# final_schematic.net
KiCad netlist of a schematic drawn in EAGLE
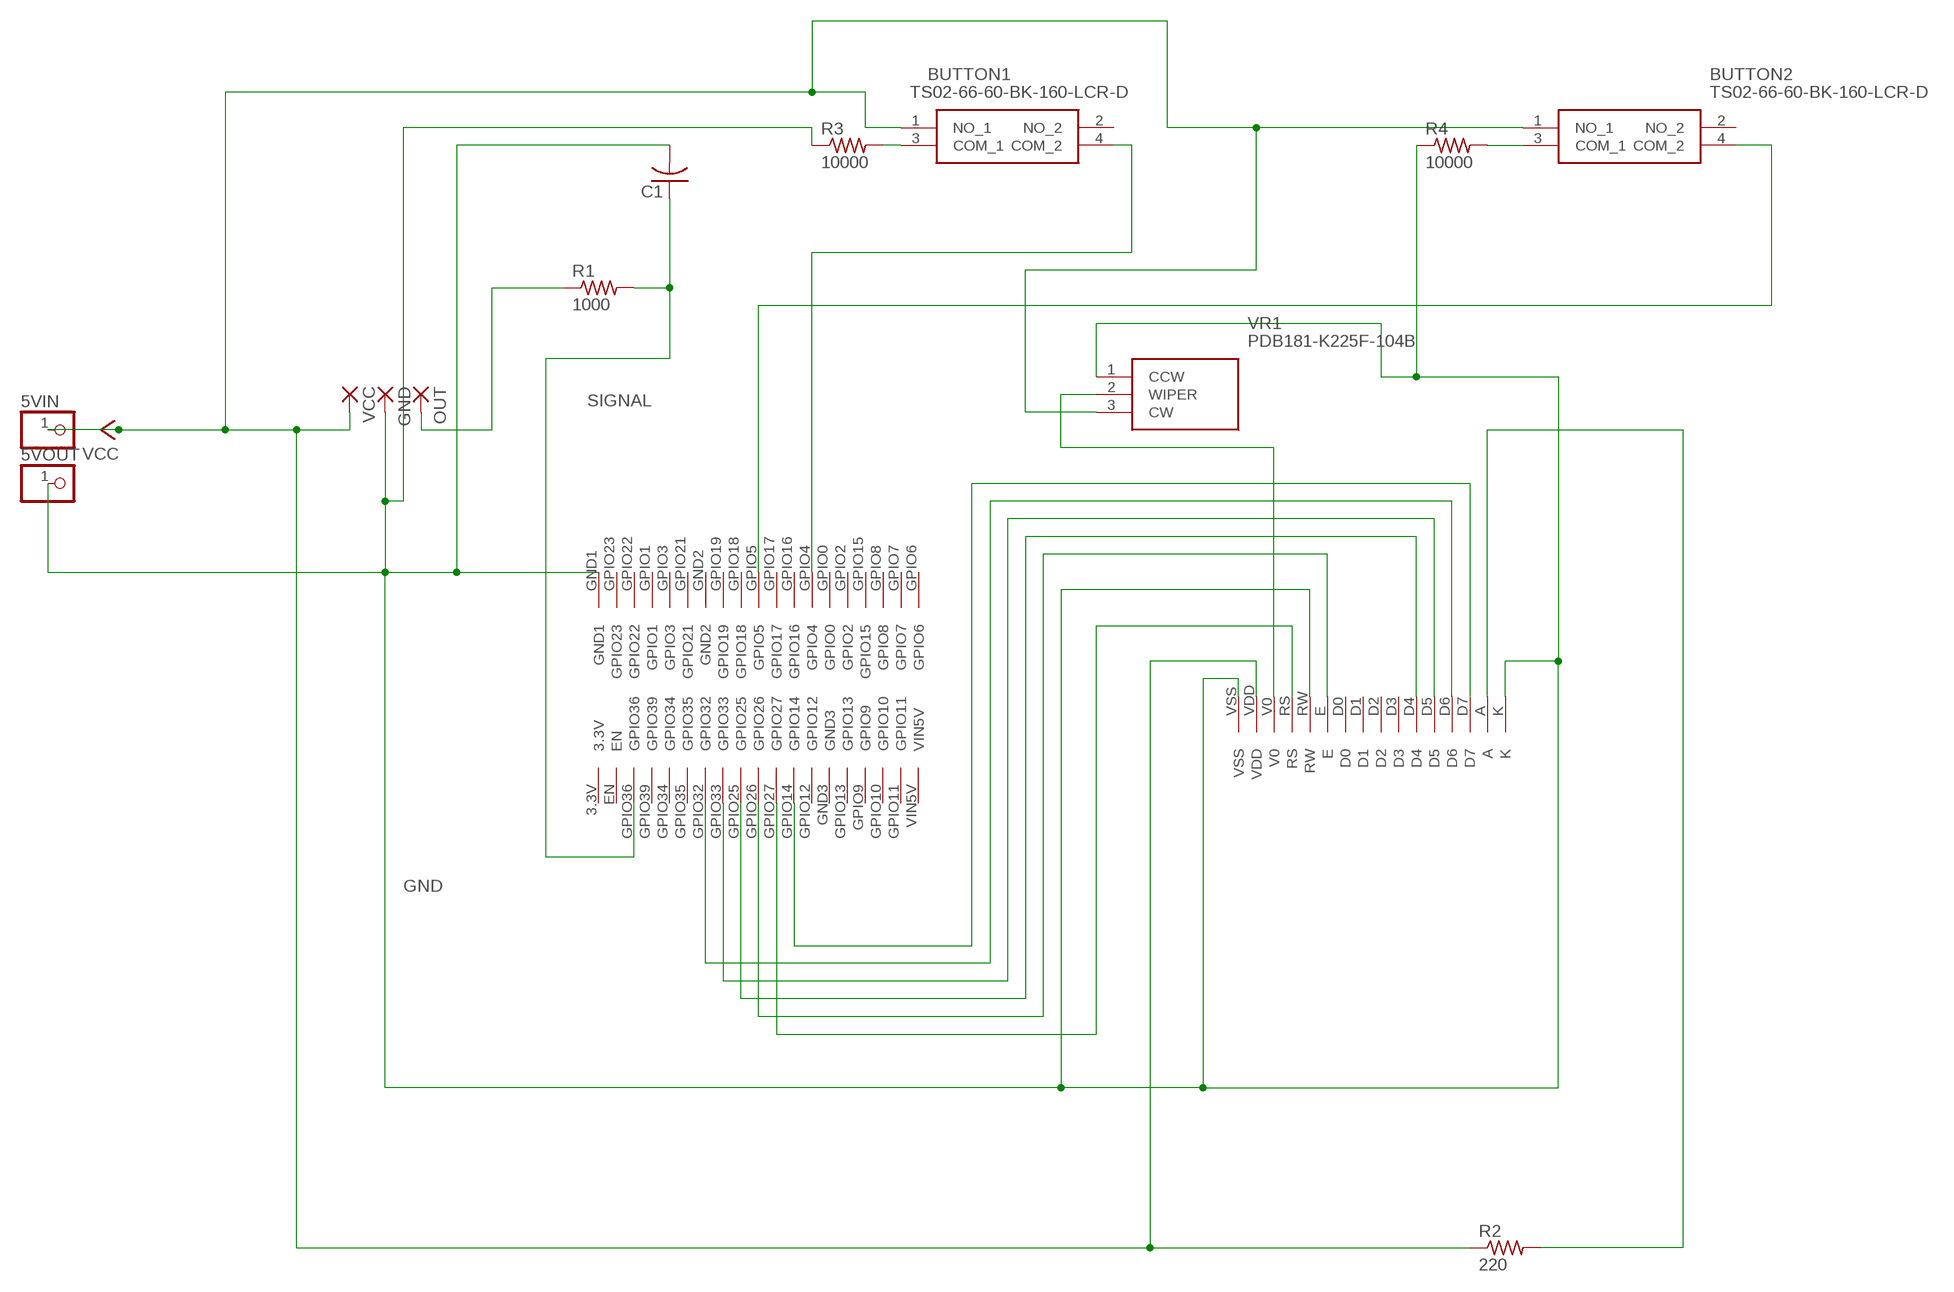
[diagram p0: schematic, sheet 1]

(export (version "E")
  (design (tool "Eeschema 10.0.6"))
  (components
    (comp (ref "5VIN")
      (value "PINHD-1X1")
      (footprint "eagle-import:1X01")
      (libsource (lib "eagle-import") (part "PINHD-1X1"))
    )
    (comp (ref "5VOUT")
      (value "PINHD-1X1")
      (footprint "eagle-import:1X01")
      (libsource (lib "eagle-import") (part "PINHD-1X1"))
    )
    (comp (ref "BUTTON1")
      (value "TS02-66-60-BK-160-LCR-D")
      (footprint "eagle-import:TS026660BK160LCRD")
      (fields (field (name "MOUSER_PART_NUMBER") "179-TS026660BK160LCR"))
      (libsource (lib "eagle-import") (part "TS02-66-60-BK-160-LCR-D"))
    )
    (comp (ref "BUTTON2")
      (value "TS02-66-60-BK-160-LCR-D")
      (footprint "eagle-import:TS026660BK160LCRD")
      (fields (field (name "MOUSER_PART_NUMBER") "179-TS026660BK160LCR"))
      (libsource (lib "eagle-import") (part "TS02-66-60-BK-160-LCR-D"))
    )
    (comp (ref "C1")
      (value "C-USC0805")
      (footprint "eagle-import:C0805")
      (libsource (lib "eagle-import") (part "C-USC0805"))
    )
    (comp (ref "GND")
      (value "1,6/0,8")
      (footprint "eagle-import:1,6_0,8")
      (libsource (lib "eagle-import") (part "1,6/0,8"))
    )
    (comp (ref "OUT")
      (value "1,6/0,8")
      (footprint "eagle-import:1,6_0,8")
      (libsource (lib "eagle-import") (part "1,6/0,8"))
    )
    (comp (ref "R1")
      (value "1000")
      (footprint "eagle-import:R0805")
      (libsource (lib "eagle-import") (part "R-US_R0805"))
    )
    (comp (ref "R2")
      (value "220")
      (footprint "eagle-import:R0805")
      (libsource (lib "eagle-import") (part "R-US_R0805"))
    )
    (comp (ref "R3")
      (value "10000")
      (footprint "eagle-import:R0805")
      (libsource (lib "eagle-import") (part "R-US_R0805"))
    )
    (comp (ref "R4")
      (value "10000")
      (footprint "eagle-import:R0805")
      (libsource (lib "eagle-import") (part "R-US_R0805"))
    )
    (comp (ref "U$1")
      (value "HILETGO")
      (footprint "eagle-import:HILETGO")
      (libsource (lib "eagle-import") (part "HILETGO"))
    )
    (comp (ref "U$2")
      (value "LCD")
      (footprint "eagle-import:LCD")
      (libsource (lib "eagle-import") (part "LCD"))
    )
    (comp (ref "VCC")
      (value "1,6/0,8")
      (footprint "eagle-import:1,6_0,8")
      (libsource (lib "eagle-import") (part "1,6/0,8"))
    )
    (comp (ref "VR1")
      (value "PDB181-K225F-104B")
      (footprint "eagle-import:PDB181K225F104B")
      (fields (field (name "MOUSER_PART_NUMBER") "652-PDB181-K225F104B"))
      (libsource (lib "eagle-import") (part "PDB181-K225F-104B"))
    )
  )
  (nets
    (net (code "1") (name "/GND") (class "Default")
      (node (ref "5VOUT") (pin "1") (pinfunction "1_1") (pintype "passive"))
      (node (ref "C1") (pin "2") (pinfunction "2_2") (pintype "passive"))
      (node (ref "GND") (pin "1") (pinfunction "P_1") (pintype "passive"))
      (node (ref "R3") (pin "1") (pinfunction "1_1") (pintype "passive"))
      (node (ref "R4") (pin "1") (pinfunction "1_1") (pintype "passive"))
      (node (ref "U$1") (pin "GND1") (pinfunction "GND1_GND1") (pintype "bidirectional"))
      (node (ref "U$2") (pin "K") (pinfunction "K_K") (pintype "bidirectional"))
      (node (ref "U$2") (pin "RW") (pinfunction "RW_RW") (pintype "bidirectional"))
      (node (ref "U$2") (pin "VSS") (pinfunction "VSS_VSS") (pintype "bidirectional"))
      (node (ref "VR1") (pin "1") (pinfunction "CCW_1") (pintype "bidirectional"))
    )
    (net (code "2") (name "/SIGNAL") (class "Default")
      (node (ref "C1") (pin "1") (pinfunction "1_1") (pintype "passive"))
      (node (ref "R1") (pin "2") (pinfunction "2_2") (pintype "passive"))
      (node (ref "U$1") (pin "GPIO36") (pinfunction "GPIO36_GPIO36") (pintype "bidirectional"))
    )
    (net (code "3") (name "Net-(BUTTON1-COM_1)") (class "Default")
      (node (ref "BUTTON1") (pin "3") (pinfunction "COM_1_3") (pintype "bidirectional"))
      (node (ref "R3") (pin "2") (pinfunction "2_2") (pintype "passive"))
    )
    (net (code "4") (name "Net-(BUTTON1-COM_2)") (class "Default")
      (node (ref "BUTTON1") (pin "4") (pinfunction "COM_2_4") (pintype "bidirectional"))
      (node (ref "U$1") (pin "GPIO4") (pinfunction "GPIO4_GPIO4") (pintype "bidirectional"))
    )
    (net (code "5") (name "Net-(BUTTON2-COM_1)") (class "Default")
      (node (ref "BUTTON2") (pin "3") (pinfunction "COM_1_3") (pintype "bidirectional"))
      (node (ref "R4") (pin "2") (pinfunction "2_2") (pintype "passive"))
    )
    (net (code "6") (name "Net-(BUTTON2-COM_2)") (class "Default")
      (node (ref "BUTTON2") (pin "4") (pinfunction "COM_2_4") (pintype "bidirectional"))
      (node (ref "U$1") (pin "GPIO5") (pinfunction "GPIO5_GPIO5") (pintype "bidirectional"))
    )
    (net (code "7") (name "Net-(OUT-P)") (class "Default")
      (node (ref "OUT") (pin "1") (pinfunction "P_1") (pintype "passive"))
      (node (ref "R1") (pin "1") (pinfunction "1_1") (pintype "passive"))
    )
    (net (code "8") (name "Net-(R2-Pad2)") (class "Default")
      (node (ref "R2") (pin "2") (pinfunction "2_2") (pintype "passive"))
      (node (ref "U$2") (pin "A") (pinfunction "A_A") (pintype "bidirectional"))
    )
    (net (code "9") (name "Net-(U$1-PadGPIO14)") (class "Default")
      (node (ref "U$1") (pin "GPIO14") (pinfunction "GPIO14_GPIO14") (pintype "bidirectional"))
      (node (ref "U$2") (pin "D7") (pinfunction "D7_D7") (pintype "bidirectional"))
    )
    (net (code "10") (name "Net-(U$1-PadGPIO25)") (class "Default")
      (node (ref "U$1") (pin "GPIO25") (pinfunction "GPIO25_GPIO25") (pintype "bidirectional"))
      (node (ref "U$2") (pin "D4") (pinfunction "D4_D4") (pintype "bidirectional"))
    )
    (net (code "11") (name "Net-(U$1-PadGPIO26)") (class "Default")
      (node (ref "U$1") (pin "GPIO26") (pinfunction "GPIO26_GPIO26") (pintype "bidirectional"))
      (node (ref "U$2") (pin "E") (pinfunction "E_E") (pintype "bidirectional"))
    )
    (net (code "12") (name "Net-(U$1-PadGPIO27)") (class "Default")
      (node (ref "U$1") (pin "GPIO27") (pinfunction "GPIO27_GPIO27") (pintype "bidirectional"))
      (node (ref "U$2") (pin "RS") (pinfunction "RS_RS") (pintype "bidirectional"))
    )
    (net (code "13") (name "Net-(U$1-PadGPIO32)") (class "Default")
      (node (ref "U$1") (pin "GPIO32") (pinfunction "GPIO32_GPIO32") (pintype "bidirectional"))
      (node (ref "U$2") (pin "D6") (pinfunction "D6_D6") (pintype "bidirectional"))
    )
    (net (code "14") (name "Net-(U$1-PadGPIO33)") (class "Default")
      (node (ref "U$1") (pin "GPIO33") (pinfunction "GPIO33_GPIO33") (pintype "bidirectional"))
      (node (ref "U$2") (pin "D5") (pinfunction "D5_D5") (pintype "bidirectional"))
    )
    (net (code "15") (name "Net-(VR1-WIPER)") (class "Default")
      (node (ref "U$2") (pin "V0") (pinfunction "V0_V0") (pintype "bidirectional"))
      (node (ref "VR1") (pin "2") (pinfunction "WIPER_2") (pintype "bidirectional"))
    )
    (net (code "16") (name "VCC") (class "Default")
      (node (ref "5VIN") (pin "1") (pinfunction "1_1") (pintype "passive"))
      (node (ref "BUTTON1") (pin "1") (pinfunction "NO_1_1") (pintype "bidirectional"))
      (node (ref "BUTTON2") (pin "1") (pinfunction "NO_1_1") (pintype "bidirectional"))
      (node (ref "R2") (pin "1") (pinfunction "1_1") (pintype "passive"))
      (node (ref "U$2") (pin "VDD") (pinfunction "VDD_VDD") (pintype "bidirectional"))
      (node (ref "VCC") (pin "1") (pinfunction "P_1") (pintype "passive"))
      (node (ref "VR1") (pin "3") (pinfunction "CW_3") (pintype "bidirectional"))
    )
    (net (code "17") (name "unconnected-(BUTTON1-NO_2-Pad2)") (class "Default")
      (node (ref "BUTTON1") (pin "2") (pinfunction "NO_2_2") (pintype "bidirectional"))
    )
    (net (code "18") (name "unconnected-(BUTTON2-NO_2-Pad2)") (class "Default")
      (node (ref "BUTTON2") (pin "2") (pinfunction "NO_2_2") (pintype "bidirectional"))
    )
    (net (code "19") (name "unconnected-(U$1-Pad3.3V)") (class "Default")
      (node (ref "U$1") (pin "3.3V") (pinfunction "3.3V_3.3V") (pintype "bidirectional"))
    )
    (net (code "20") (name "unconnected-(U$1-PadEN)") (class "Default")
      (node (ref "U$1") (pin "EN") (pinfunction "EN_EN") (pintype "bidirectional"))
    )
    (net (code "21") (name "unconnected-(U$1-PadGND2)") (class "Default")
      (node (ref "U$1") (pin "GND2") (pinfunction "GND2_GND2") (pintype "bidirectional"))
    )
    (net (code "22") (name "unconnected-(U$1-PadGND3)") (class "Default")
      (node (ref "U$1") (pin "GND3") (pinfunction "GND3_GND3") (pintype "bidirectional"))
    )
    (net (code "23") (name "unconnected-(U$1-PadGPIO0)") (class "Default")
      (node (ref "U$1") (pin "GPIO0") (pinfunction "GPIO0_GPIO0") (pintype "bidirectional"))
    )
    (net (code "24") (name "unconnected-(U$1-PadGPIO1)") (class "Default")
      (node (ref "U$1") (pin "GPIO1") (pinfunction "GPIO1_GPIO1") (pintype "bidirectional"))
    )
    (net (code "25") (name "unconnected-(U$1-PadGPIO2)") (class "Default")
      (node (ref "U$1") (pin "GPIO2") (pinfunction "GPIO2_GPIO2") (pintype "bidirectional"))
    )
    (net (code "26") (name "unconnected-(U$1-PadGPIO3)") (class "Default")
      (node (ref "U$1") (pin "GPIO3") (pinfunction "GPIO3_GPIO3") (pintype "bidirectional"))
    )
    (net (code "27") (name "unconnected-(U$1-PadGPIO6)") (class "Default")
      (node (ref "U$1") (pin "GPIO6") (pinfunction "GPIO6_GPIO6") (pintype "bidirectional"))
    )
    (net (code "28") (name "unconnected-(U$1-PadGPIO7)") (class "Default")
      (node (ref "U$1") (pin "GPIO7") (pinfunction "GPIO7_GPIO7") (pintype "bidirectional"))
    )
    (net (code "29") (name "unconnected-(U$1-PadGPIO8)") (class "Default")
      (node (ref "U$1") (pin "GPIO8") (pinfunction "GPIO8_GPIO8") (pintype "bidirectional"))
    )
    (net (code "30") (name "unconnected-(U$1-PadGPIO9)") (class "Default")
      (node (ref "U$1") (pin "GPIO9") (pinfunction "GPIO9_GPIO9") (pintype "bidirectional"))
    )
    (net (code "31") (name "unconnected-(U$1-PadGPIO10)") (class "Default")
      (node (ref "U$1") (pin "GPIO10") (pinfunction "GPIO10_GPIO10") (pintype "bidirectional"))
    )
    (net (code "32") (name "unconnected-(U$1-PadGPIO11)") (class "Default")
      (node (ref "U$1") (pin "GPIO11") (pinfunction "GPIO11_GPIO11") (pintype "bidirectional"))
    )
    (net (code "33") (name "unconnected-(U$1-PadGPIO12)") (class "Default")
      (node (ref "U$1") (pin "GPIO12") (pinfunction "GPIO12_GPIO12") (pintype "bidirectional"))
    )
    (net (code "34") (name "unconnected-(U$1-PadGPIO13)") (class "Default")
      (node (ref "U$1") (pin "GPIO13") (pinfunction "GPIO13_GPIO13") (pintype "bidirectional"))
    )
    (net (code "35") (name "unconnected-(U$1-PadGPIO15)") (class "Default")
      (node (ref "U$1") (pin "GPIO15") (pinfunction "GPIO15_GPIO15") (pintype "bidirectional"))
    )
    (net (code "36") (name "unconnected-(U$1-PadGPIO16)") (class "Default")
      (node (ref "U$1") (pin "GPIO16") (pinfunction "GPIO16_GPIO16") (pintype "bidirectional"))
    )
    (net (code "37") (name "unconnected-(U$1-PadGPIO17)") (class "Default")
      (node (ref "U$1") (pin "GPIO17") (pinfunction "GPIO17_GPIO17") (pintype "bidirectional"))
    )
    (net (code "38") (name "unconnected-(U$1-PadGPIO18)") (class "Default")
      (node (ref "U$1") (pin "GPIO18") (pinfunction "GPIO18_GPIO18") (pintype "bidirectional"))
    )
    (net (code "39") (name "unconnected-(U$1-PadGPIO19)") (class "Default")
      (node (ref "U$1") (pin "GPIO19") (pinfunction "GPIO19_GPIO19") (pintype "bidirectional"))
    )
    (net (code "40") (name "unconnected-(U$1-PadGPIO21)") (class "Default")
      (node (ref "U$1") (pin "GPIO21") (pinfunction "GPIO21_GPIO21") (pintype "bidirectional"))
    )
    (net (code "41") (name "unconnected-(U$1-PadGPIO22)") (class "Default")
      (node (ref "U$1") (pin "GPIO22") (pinfunction "GPIO22_GPIO22") (pintype "bidirectional"))
    )
    (net (code "42") (name "unconnected-(U$1-PadGPIO23)") (class "Default")
      (node (ref "U$1") (pin "GPIO23") (pinfunction "GPIO23_GPIO23") (pintype "bidirectional"))
    )
    (net (code "43") (name "unconnected-(U$1-PadGPIO34)") (class "Default")
      (node (ref "U$1") (pin "GPIO34") (pinfunction "GPIO34_GPIO34") (pintype "bidirectional"))
    )
    (net (code "44") (name "unconnected-(U$1-PadGPIO35)") (class "Default")
      (node (ref "U$1") (pin "GPIO35") (pinfunction "GPIO35_GPIO35") (pintype "bidirectional"))
    )
    (net (code "45") (name "unconnected-(U$1-PadGPIO39)") (class "Default")
      (node (ref "U$1") (pin "GPIO39") (pinfunction "GPIO39_GPIO39") (pintype "bidirectional"))
    )
    (net (code "46") (name "unconnected-(U$1-PadVIN5V)") (class "Default")
      (node (ref "U$1") (pin "VIN5V") (pinfunction "VIN5V_VIN5V") (pintype "bidirectional"))
    )
    (net (code "47") (name "unconnected-(U$2-PadD0)") (class "Default")
      (node (ref "U$2") (pin "D0") (pinfunction "D0_D0") (pintype "bidirectional"))
    )
    (net (code "48") (name "unconnected-(U$2-PadD1)") (class "Default")
      (node (ref "U$2") (pin "D1") (pinfunction "D1_D1") (pintype "bidirectional"))
    )
    (net (code "49") (name "unconnected-(U$2-PadD2)") (class "Default")
      (node (ref "U$2") (pin "D2") (pinfunction "D2_D2") (pintype "bidirectional"))
    )
    (net (code "50") (name "unconnected-(U$2-PadD3)") (class "Default")
      (node (ref "U$2") (pin "D3") (pinfunction "D3_D3") (pintype "bidirectional"))
    )
  )
)
